# slaveV10a.net
KiCad netlist of a schematic drawn in EAGLE
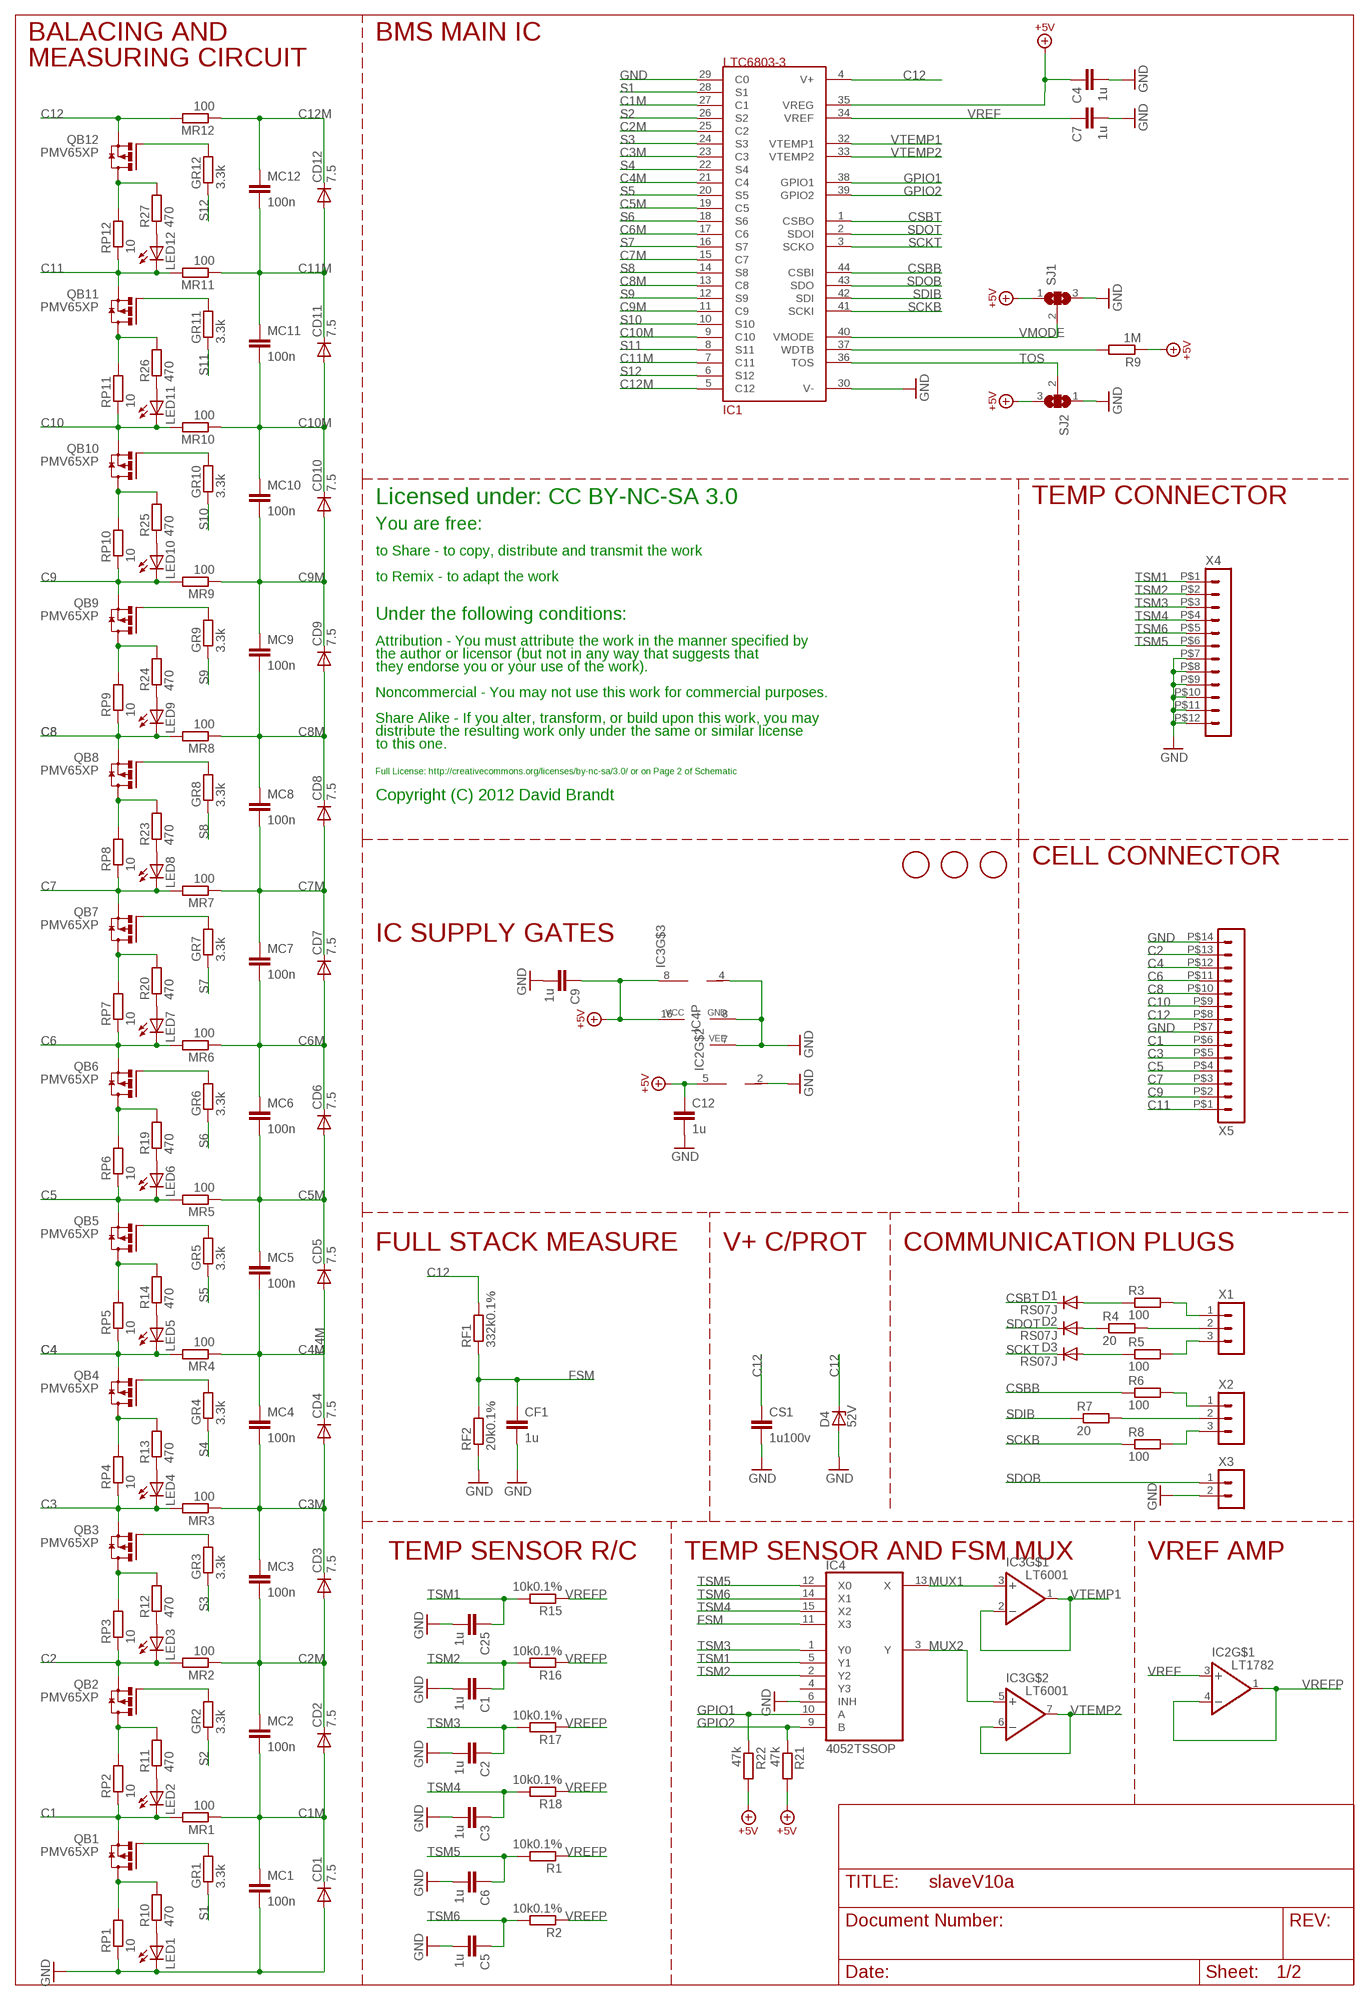
[diagram p0: schematic, sheet 1]
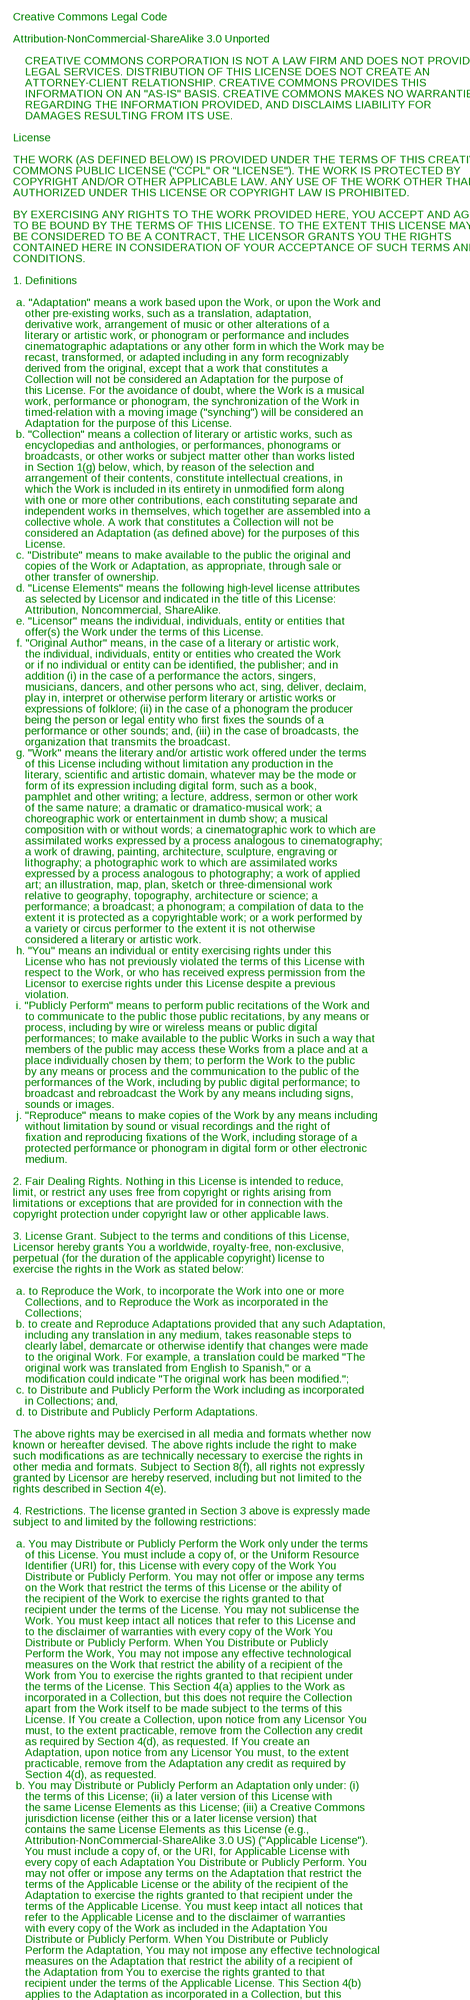
[diagram p1: schematic, sheet 2, part 1 of 2]
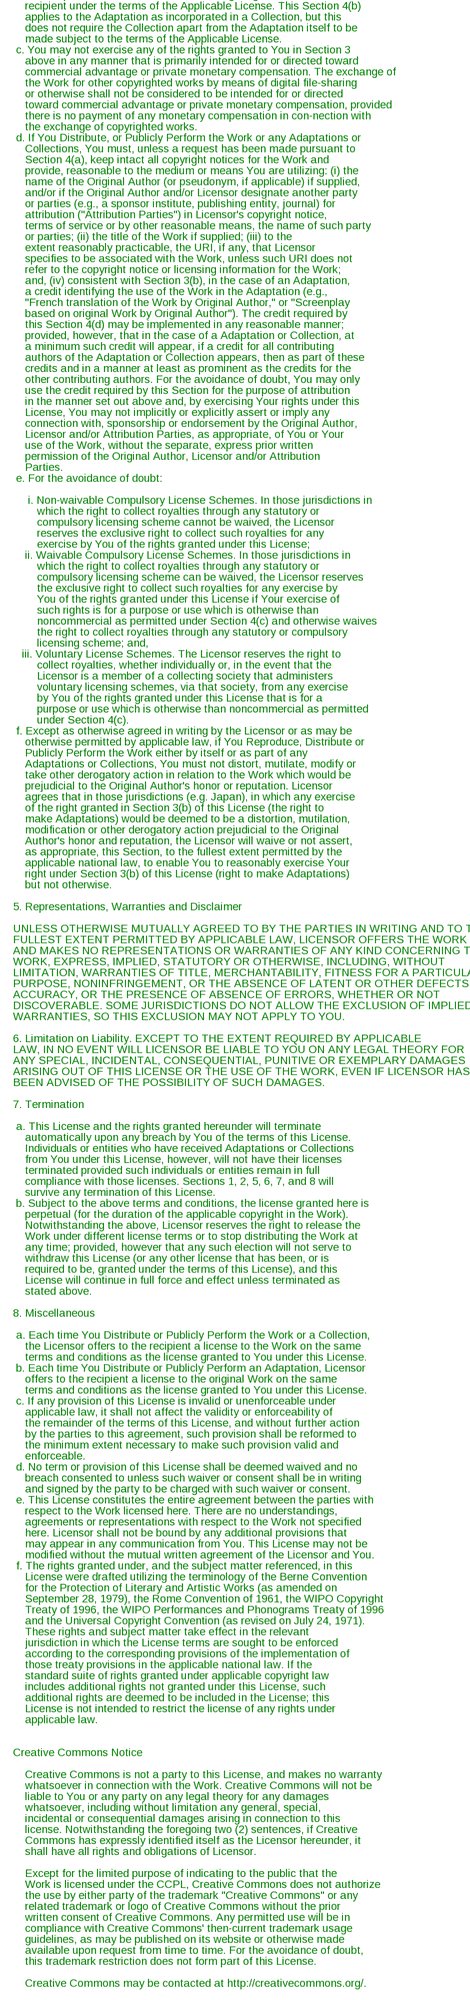
[diagram p2: schematic, sheet 2, part 2 of 2]

(export (version "E")
  (design (tool "Eeschema 10.0.6"))
  (components
    (comp (ref "C1")
      (value "1u")
      (footprint "eagle-import:C0603")
      (libsource (lib "eagle-import") (part "C-EUC0603"))
    )
    (comp (ref "C2")
      (value "1u")
      (footprint "eagle-import:C0603")
      (libsource (lib "eagle-import") (part "C-EUC0603"))
    )
    (comp (ref "C3")
      (value "1u")
      (footprint "eagle-import:C0603")
      (libsource (lib "eagle-import") (part "C-EUC0603"))
    )
    (comp (ref "C4")
      (value "1u")
      (footprint "eagle-import:C0603")
      (libsource (lib "eagle-import") (part "C-EUC0603"))
    )
    (comp (ref "C5")
      (value "1u")
      (footprint "eagle-import:C0603")
      (libsource (lib "eagle-import") (part "C-EUC0603"))
    )
    (comp (ref "C6")
      (value "1u")
      (footprint "eagle-import:C0603")
      (libsource (lib "eagle-import") (part "C-EUC0603"))
    )
    (comp (ref "C7")
      (value "1u")
      (footprint "eagle-import:C0603")
      (libsource (lib "eagle-import") (part "C-EUC0603"))
    )
    (comp (ref "C9")
      (value "1u")
      (footprint "eagle-import:C0603")
      (libsource (lib "eagle-import") (part "C-EUC0603"))
    )
    (comp (ref "C12")
      (value "1u")
      (footprint "eagle-import:C0603")
      (libsource (lib "eagle-import") (part "C-EUC0603"))
    )
    (comp (ref "C25")
      (value "1u")
      (footprint "eagle-import:C0603")
      (libsource (lib "eagle-import") (part "C-EUC0603"))
    )
    (comp (ref "CD1")
      (value "7.5")
      (footprint "eagle-import:SOD323-W")
      (libsource (lib "eagle-import") (part "DIODE-SOD323-W"))
    )
    (comp (ref "CD2")
      (value "7.5")
      (footprint "eagle-import:SOD323-W")
      (libsource (lib "eagle-import") (part "DIODE-SOD323-W"))
    )
    (comp (ref "CD3")
      (value "7.5")
      (footprint "eagle-import:SOD323-W")
      (libsource (lib "eagle-import") (part "DIODE-SOD323-W"))
    )
    (comp (ref "CD4")
      (value "7.5")
      (footprint "eagle-import:SOD323-W")
      (libsource (lib "eagle-import") (part "DIODE-SOD323-W"))
    )
    (comp (ref "CD5")
      (value "7.5")
      (footprint "eagle-import:SOD323-W")
      (libsource (lib "eagle-import") (part "DIODE-SOD323-W"))
    )
    (comp (ref "CD6")
      (value "7.5")
      (footprint "eagle-import:SOD323-W")
      (libsource (lib "eagle-import") (part "DIODE-SOD323-W"))
    )
    (comp (ref "CD7")
      (value "7.5")
      (footprint "eagle-import:SOD323-W")
      (libsource (lib "eagle-import") (part "DIODE-SOD323-W"))
    )
    (comp (ref "CD8")
      (value "7.5")
      (footprint "eagle-import:SOD323-W")
      (libsource (lib "eagle-import") (part "DIODE-SOD323-W"))
    )
    (comp (ref "CD9")
      (value "7.5")
      (footprint "eagle-import:SOD323-W")
      (libsource (lib "eagle-import") (part "DIODE-SOD323-W"))
    )
    (comp (ref "CD10")
      (value "7.5")
      (footprint "eagle-import:SOD323-W")
      (libsource (lib "eagle-import") (part "DIODE-SOD323-W"))
    )
    (comp (ref "CD11")
      (value "7.5")
      (footprint "eagle-import:SOD323-W")
      (libsource (lib "eagle-import") (part "DIODE-SOD323-W"))
    )
    (comp (ref "CD12")
      (value "7.5")
      (footprint "eagle-import:SOD323-W")
      (libsource (lib "eagle-import") (part "DIODE-SOD323-W"))
    )
    (comp (ref "CF1")
      (value "1u")
      (footprint "eagle-import:C0603")
      (libsource (lib "eagle-import") (part "C-EUC0603"))
    )
    (comp (ref "CS1")
      (value "1u100v")
      (footprint "eagle-import:C1206K")
      (libsource (lib "eagle-import") (part "C-EUC1206K"))
    )
    (comp (ref "D1")
      (value "RS07J")
      (footprint "eagle-import:DO-219AB")
      (libsource (lib "eagle-import") (part "RS07J"))
    )
    (comp (ref "D2")
      (value "RS07J")
      (footprint "eagle-import:DO-219AB")
      (libsource (lib "eagle-import") (part "RS07J"))
    )
    (comp (ref "D3")
      (value "RS07J")
      (footprint "eagle-import:DO-219AB")
      (libsource (lib "eagle-import") (part "RS07J"))
    )
    (comp (ref "D4")
      (value "52V")
      (footprint "eagle-import:SOD123")
      (libsource (lib "eagle-import") (part "ZENER-DIODESOD123"))
    )
    (comp (ref "GR1")
      (value "3.3k")
      (footprint "eagle-import:R0603")
      (libsource (lib "eagle-import") (part "rcl_R-EU_R0603"))
    )
    (comp (ref "GR2")
      (value "3.3k")
      (footprint "eagle-import:R0603")
      (libsource (lib "eagle-import") (part "rcl_R-EU_R0603"))
    )
    (comp (ref "GR3")
      (value "3.3k")
      (footprint "eagle-import:R0603")
      (libsource (lib "eagle-import") (part "rcl_R-EU_R0603"))
    )
    (comp (ref "GR4")
      (value "3.3k")
      (footprint "eagle-import:R0603")
      (libsource (lib "eagle-import") (part "rcl_R-EU_R0603"))
    )
    (comp (ref "GR5")
      (value "3.3k")
      (footprint "eagle-import:R0603")
      (libsource (lib "eagle-import") (part "rcl_R-EU_R0603"))
    )
    (comp (ref "GR6")
      (value "3.3k")
      (footprint "eagle-import:R0603")
      (libsource (lib "eagle-import") (part "rcl_R-EU_R0603"))
    )
    (comp (ref "GR7")
      (value "3.3k")
      (footprint "eagle-import:R0603")
      (libsource (lib "eagle-import") (part "rcl_R-EU_R0603"))
    )
    (comp (ref "GR8")
      (value "3.3k")
      (footprint "eagle-import:R0603")
      (libsource (lib "eagle-import") (part "rcl_R-EU_R0603"))
    )
    (comp (ref "GR9")
      (value "3.3k")
      (footprint "eagle-import:R0603")
      (libsource (lib "eagle-import") (part "rcl_R-EU_R0603"))
    )
    (comp (ref "GR10")
      (value "3.3k")
      (footprint "eagle-import:R0603")
      (libsource (lib "eagle-import") (part "rcl_R-EU_R0603"))
    )
    (comp (ref "GR11")
      (value "3.3k")
      (footprint "eagle-import:R0603")
      (libsource (lib "eagle-import") (part "rcl_R-EU_R0603"))
    )
    (comp (ref "GR12")
      (value "3.3k")
      (footprint "eagle-import:R0603")
      (libsource (lib "eagle-import") (part "rcl_R-EU_R0603"))
    )
    (comp (ref "IC1")
      (value "LTC6803-3")
      (footprint "eagle-import:44SSOP")
      (libsource (lib "eagle-import") (part "LTC6803-3"))
    )
    (comp (ref "IC2")
      (value "LT1782")
      (footprint "eagle-import:SOT23-5")
      (libsource (lib "eagle-import") (part "LT1782"))
    )
    (comp (ref "IC3")
      (value "LT6001")
      (footprint "eagle-import:MS8")
      (libsource (lib "eagle-import") (part "LT6004"))
    )
    (comp (ref "IC4")
      (value "4052TSSOP")
      (footprint "eagle-import:TSSOP16")
      (libsource (lib "eagle-import") (part "4052TSSOP"))
    )
    (comp (ref "LED1")
      (value "LEDCHIPLED_0805")
      (footprint "eagle-import:CHIPLED_0805")
      (libsource (lib "eagle-import") (part "LEDCHIPLED_0805"))
    )
    (comp (ref "LED2")
      (value "LEDCHIPLED_0805")
      (footprint "eagle-import:CHIPLED_0805")
      (libsource (lib "eagle-import") (part "LEDCHIPLED_0805"))
    )
    (comp (ref "LED3")
      (value "LEDCHIPLED_0805")
      (footprint "eagle-import:CHIPLED_0805")
      (libsource (lib "eagle-import") (part "LEDCHIPLED_0805"))
    )
    (comp (ref "LED4")
      (value "LEDCHIPLED_0805")
      (footprint "eagle-import:CHIPLED_0805")
      (libsource (lib "eagle-import") (part "LEDCHIPLED_0805"))
    )
    (comp (ref "LED5")
      (value "LEDCHIPLED_0805")
      (footprint "eagle-import:CHIPLED_0805")
      (libsource (lib "eagle-import") (part "LEDCHIPLED_0805"))
    )
    (comp (ref "LED6")
      (value "LEDCHIPLED_0805")
      (footprint "eagle-import:CHIPLED_0805")
      (libsource (lib "eagle-import") (part "LEDCHIPLED_0805"))
    )
    (comp (ref "LED7")
      (value "LEDCHIPLED_0805")
      (footprint "eagle-import:CHIPLED_0805")
      (libsource (lib "eagle-import") (part "LEDCHIPLED_0805"))
    )
    (comp (ref "LED8")
      (value "LEDCHIPLED_0805")
      (footprint "eagle-import:CHIPLED_0805")
      (libsource (lib "eagle-import") (part "LEDCHIPLED_0805"))
    )
    (comp (ref "LED9")
      (value "LEDCHIPLED_0805")
      (footprint "eagle-import:CHIPLED_0805")
      (libsource (lib "eagle-import") (part "LEDCHIPLED_0805"))
    )
    (comp (ref "LED10")
      (value "LEDCHIPLED_0805")
      (footprint "eagle-import:CHIPLED_0805")
      (libsource (lib "eagle-import") (part "LEDCHIPLED_0805"))
    )
    (comp (ref "LED11")
      (value "LEDCHIPLED_0805")
      (footprint "eagle-import:CHIPLED_0805")
      (libsource (lib "eagle-import") (part "LEDCHIPLED_0805"))
    )
    (comp (ref "LED12")
      (value "LEDCHIPLED_0805")
      (footprint "eagle-import:CHIPLED_0805")
      (libsource (lib "eagle-import") (part "LEDCHIPLED_0805"))
    )
    (comp (ref "MC1")
      (value "100n")
      (footprint "eagle-import:C1206")
      (libsource (lib "eagle-import") (part "C-EUC1206"))
    )
    (comp (ref "MC2")
      (value "100n")
      (footprint "eagle-import:C1206")
      (libsource (lib "eagle-import") (part "C-EUC1206"))
    )
    (comp (ref "MC3")
      (value "100n")
      (footprint "eagle-import:C1206")
      (libsource (lib "eagle-import") (part "C-EUC1206"))
    )
    (comp (ref "MC4")
      (value "100n")
      (footprint "eagle-import:C1206")
      (libsource (lib "eagle-import") (part "C-EUC1206"))
    )
    (comp (ref "MC5")
      (value "100n")
      (footprint "eagle-import:C1206")
      (libsource (lib "eagle-import") (part "C-EUC1206"))
    )
    (comp (ref "MC6")
      (value "100n")
      (footprint "eagle-import:C1206")
      (libsource (lib "eagle-import") (part "C-EUC1206"))
    )
    (comp (ref "MC7")
      (value "100n")
      (footprint "eagle-import:C1206")
      (libsource (lib "eagle-import") (part "C-EUC1206"))
    )
    (comp (ref "MC8")
      (value "100n")
      (footprint "eagle-import:C1206")
      (libsource (lib "eagle-import") (part "C-EUC1206"))
    )
    (comp (ref "MC9")
      (value "100n")
      (footprint "eagle-import:C1206")
      (libsource (lib "eagle-import") (part "C-EUC1206"))
    )
    (comp (ref "MC10")
      (value "100n")
      (footprint "eagle-import:C1206")
      (libsource (lib "eagle-import") (part "C-EUC1206"))
    )
    (comp (ref "MC11")
      (value "100n")
      (footprint "eagle-import:C1206")
      (libsource (lib "eagle-import") (part "C-EUC1206"))
    )
    (comp (ref "MC12")
      (value "100n")
      (footprint "eagle-import:C1206")
      (libsource (lib "eagle-import") (part "C-EUC1206"))
    )
    (comp (ref "MR1")
      (value "100")
      (footprint "eagle-import:R0603")
      (libsource (lib "eagle-import") (part "rcl_R-EU_R0603"))
    )
    (comp (ref "MR2")
      (value "100")
      (footprint "eagle-import:R0603")
      (libsource (lib "eagle-import") (part "rcl_R-EU_R0603"))
    )
    (comp (ref "MR3")
      (value "100")
      (footprint "eagle-import:R0603")
      (libsource (lib "eagle-import") (part "rcl_R-EU_R0603"))
    )
    (comp (ref "MR4")
      (value "100")
      (footprint "eagle-import:R0603")
      (libsource (lib "eagle-import") (part "rcl_R-EU_R0603"))
    )
    (comp (ref "MR5")
      (value "100")
      (footprint "eagle-import:R0603")
      (libsource (lib "eagle-import") (part "rcl_R-EU_R0603"))
    )
    (comp (ref "MR6")
      (value "100")
      (footprint "eagle-import:R0603")
      (libsource (lib "eagle-import") (part "rcl_R-EU_R0603"))
    )
    (comp (ref "MR7")
      (value "100")
      (footprint "eagle-import:R0603")
      (libsource (lib "eagle-import") (part "rcl_R-EU_R0603"))
    )
    (comp (ref "MR8")
      (value "100")
      (footprint "eagle-import:R0603")
      (libsource (lib "eagle-import") (part "rcl_R-EU_R0603"))
    )
    (comp (ref "MR9")
      (value "100")
      (footprint "eagle-import:R0603")
      (libsource (lib "eagle-import") (part "rcl_R-EU_R0603"))
    )
    (comp (ref "MR10")
      (value "100")
      (footprint "eagle-import:R0603")
      (libsource (lib "eagle-import") (part "rcl_R-EU_R0603"))
    )
    (comp (ref "MR11")
      (value "100")
      (footprint "eagle-import:R0603")
      (libsource (lib "eagle-import") (part "rcl_R-EU_R0603"))
    )
    (comp (ref "MR12")
      (value "100")
      (footprint "eagle-import:R0603")
      (libsource (lib "eagle-import") (part "rcl_R-EU_R0603"))
    )
    (comp (ref "QB1")
      (value "PMV65XP")
      (footprint "eagle-import:SUPER-SOT3")
      (libsource (lib "eagle-import") (part "FDN360P"))
    )
    (comp (ref "QB2")
      (value "PMV65XP")
      (footprint "eagle-import:SUPER-SOT3")
      (libsource (lib "eagle-import") (part "FDN360P"))
    )
    (comp (ref "QB3")
      (value "PMV65XP")
      (footprint "eagle-import:SUPER-SOT3")
      (libsource (lib "eagle-import") (part "FDN360P"))
    )
    (comp (ref "QB4")
      (value "PMV65XP")
      (footprint "eagle-import:SUPER-SOT3")
      (libsource (lib "eagle-import") (part "FDN360P"))
    )
    (comp (ref "QB5")
      (value "PMV65XP")
      (footprint "eagle-import:SUPER-SOT3")
      (libsource (lib "eagle-import") (part "FDN360P"))
    )
    (comp (ref "QB6")
      (value "PMV65XP")
      (footprint "eagle-import:SUPER-SOT3")
      (libsource (lib "eagle-import") (part "FDN360P"))
    )
    (comp (ref "QB7")
      (value "PMV65XP")
      (footprint "eagle-import:SUPER-SOT3")
      (libsource (lib "eagle-import") (part "FDN360P"))
    )
    (comp (ref "QB8")
      (value "PMV65XP")
      (footprint "eagle-import:SUPER-SOT3")
      (libsource (lib "eagle-import") (part "FDN360P"))
    )
    (comp (ref "QB9")
      (value "PMV65XP")
      (footprint "eagle-import:SUPER-SOT3")
      (libsource (lib "eagle-import") (part "FDN360P"))
    )
    (comp (ref "QB10")
      (value "PMV65XP")
      (footprint "eagle-import:SUPER-SOT3")
      (libsource (lib "eagle-import") (part "FDN360P"))
    )
    (comp (ref "QB11")
      (value "PMV65XP")
      (footprint "eagle-import:SUPER-SOT3")
      (libsource (lib "eagle-import") (part "FDN360P"))
    )
    (comp (ref "QB12")
      (value "PMV65XP")
      (footprint "eagle-import:SUPER-SOT3")
      (libsource (lib "eagle-import") (part "FDN360P"))
    )
    (comp (ref "R1")
      (value "10k0.1%")
      (footprint "eagle-import:R0603")
      (libsource (lib "eagle-import") (part "rcl_R-EU_R0603"))
    )
    (comp (ref "R2")
      (value "10k0.1%")
      (footprint "eagle-import:R0603")
      (libsource (lib "eagle-import") (part "rcl_R-EU_R0603"))
    )
    (comp (ref "R3")
      (value "100")
      (footprint "eagle-import:R0805")
      (libsource (lib "eagle-import") (part "rcl_R-EU_R0805"))
    )
    (comp (ref "R4")
      (value "20")
      (footprint "eagle-import:R0805")
      (libsource (lib "eagle-import") (part "rcl_R-EU_R0805"))
    )
    (comp (ref "R5")
      (value "100")
      (footprint "eagle-import:R0805")
      (libsource (lib "eagle-import") (part "rcl_R-EU_R0805"))
    )
    (comp (ref "R6")
      (value "100")
      (footprint "eagle-import:R0805")
      (libsource (lib "eagle-import") (part "rcl_R-EU_R0805"))
    )
    (comp (ref "R7")
      (value "20")
      (footprint "eagle-import:R0805")
      (libsource (lib "eagle-import") (part "rcl_R-EU_R0805"))
    )
    (comp (ref "R8")
      (value "100")
      (footprint "eagle-import:R0805")
      (libsource (lib "eagle-import") (part "rcl_R-EU_R0805"))
    )
    (comp (ref "R9")
      (value "1M")
      (footprint "eagle-import:R0603")
      (libsource (lib "eagle-import") (part "rcl_R-EU_R0603"))
    )
    (comp (ref "R10")
      (value "470")
      (footprint "eagle-import:R0603")
      (libsource (lib "eagle-import") (part "rcl_R-EU_R0603"))
    )
    (comp (ref "R11")
      (value "470")
      (footprint "eagle-import:R0603")
      (libsource (lib "eagle-import") (part "rcl_R-EU_R0603"))
    )
    (comp (ref "R12")
      (value "470")
      (footprint "eagle-import:R0603")
      (libsource (lib "eagle-import") (part "rcl_R-EU_R0603"))
    )
    (comp (ref "R13")
      (value "470")
      (footprint "eagle-import:R0603")
      (libsource (lib "eagle-import") (part "rcl_R-EU_R0603"))
    )
    (comp (ref "R14")
      (value "470")
      (footprint "eagle-import:R0603")
      (libsource (lib "eagle-import") (part "rcl_R-EU_R0603"))
    )
    (comp (ref "R15")
      (value "10k0.1%")
      (footprint "eagle-import:R0603")
      (libsource (lib "eagle-import") (part "rcl_R-EU_R0603"))
    )
    (comp (ref "R16")
      (value "10k0.1%")
      (footprint "eagle-import:R0603")
      (libsource (lib "eagle-import") (part "rcl_R-EU_R0603"))
    )
    (comp (ref "R17")
      (value "10k0.1%")
      (footprint "eagle-import:R0603")
      (libsource (lib "eagle-import") (part "rcl_R-EU_R0603"))
    )
    (comp (ref "R18")
      (value "10k0.1%")
      (footprint "eagle-import:R0603")
      (libsource (lib "eagle-import") (part "rcl_R-EU_R0603"))
    )
    (comp (ref "R19")
      (value "470")
      (footprint "eagle-import:R0603")
      (libsource (lib "eagle-import") (part "rcl_R-EU_R0603"))
    )
    (comp (ref "R20")
      (value "470")
      (footprint "eagle-import:R0603")
      (libsource (lib "eagle-import") (part "rcl_R-EU_R0603"))
    )
    (comp (ref "R21")
      (value "47k")
      (footprint "eagle-import:R0603")
      (libsource (lib "eagle-import") (part "rcl_R-EU_R0603"))
    )
    (comp (ref "R22")
      (value "47k")
      (footprint "eagle-import:R0603")
      (libsource (lib "eagle-import") (part "rcl_R-EU_R0603"))
    )
    (comp (ref "R23")
      (value "470")
      (footprint "eagle-import:R0603")
      (libsource (lib "eagle-import") (part "rcl_R-EU_R0603"))
    )
    (comp (ref "R24")
      (value "470")
      (footprint "eagle-import:R0603")
      (libsource (lib "eagle-import") (part "rcl_R-EU_R0603"))
    )
    (comp (ref "R25")
      (value "470")
      (footprint "eagle-import:R0603")
      (libsource (lib "eagle-import") (part "rcl_R-EU_R0603"))
    )
    (comp (ref "R26")
      (value "470")
      (footprint "eagle-import:R0603")
      (libsource (lib "eagle-import") (part "rcl_R-EU_R0603"))
    )
    (comp (ref "R27")
      (value "470")
      (footprint "eagle-import:R0603")
      (libsource (lib "eagle-import") (part "rcl_R-EU_R0603"))
    )
    (comp (ref "REF1")
      (value "FIDUCIALMOUNT")
      (footprint "eagle-import:FIDUCIA-MOUNT")
      (libsource (lib "eagle-import") (part "FIDUCIALMOUNT"))
    )
    (comp (ref "REF2")
      (value "FIDUCIALMOUNT")
      (footprint "eagle-import:FIDUCIA-MOUNT")
      (libsource (lib "eagle-import") (part "FIDUCIALMOUNT"))
    )
    (comp (ref "REF3")
      (value "FIDUCIALMOUNT")
      (footprint "eagle-import:FIDUCIA-MOUNT")
      (libsource (lib "eagle-import") (part "FIDUCIALMOUNT"))
    )
    (comp (ref "RF1")
      (value "332k0.1%")
      (footprint "eagle-import:R0603")
      (libsource (lib "eagle-import") (part "rcl_R-EU_R0603"))
    )
    (comp (ref "RF2")
      (value "20k0.1%")
      (footprint "eagle-import:R0603")
      (libsource (lib "eagle-import") (part "rcl_R-EU_R0603"))
    )
    (comp (ref "RP1")
      (value "10")
      (footprint "eagle-import:SM_3")
      (libsource (lib "eagle-import") (part "R-EU_SM_3"))
    )
    (comp (ref "RP2")
      (value "10")
      (footprint "eagle-import:SM_3")
      (libsource (lib "eagle-import") (part "R-EU_SM_3"))
    )
    (comp (ref "RP3")
      (value "10")
      (footprint "eagle-import:SM_3")
      (libsource (lib "eagle-import") (part "R-EU_SM_3"))
    )
    (comp (ref "RP4")
      (value "10")
      (footprint "eagle-import:SM_3")
      (libsource (lib "eagle-import") (part "R-EU_SM_3"))
    )
    (comp (ref "RP5")
      (value "10")
      (footprint "eagle-import:SM_3")
      (libsource (lib "eagle-import") (part "R-EU_SM_3"))
    )
    (comp (ref "RP6")
      (value "10")
      (footprint "eagle-import:SM_3")
      (libsource (lib "eagle-import") (part "R-EU_SM_3"))
    )
    (comp (ref "RP7")
      (value "10")
      (footprint "eagle-import:SM_3")
      (libsource (lib "eagle-import") (part "R-EU_SM_3"))
    )
    (comp (ref "RP8")
      (value "10")
      (footprint "eagle-import:SM_3")
      (libsource (lib "eagle-import") (part "R-EU_SM_3"))
    )
    (comp (ref "RP9")
      (value "10")
      (footprint "eagle-import:SM_3")
      (libsource (lib "eagle-import") (part "R-EU_SM_3"))
    )
    (comp (ref "RP10")
      (value "10")
      (footprint "eagle-import:SM_3")
      (libsource (lib "eagle-import") (part "R-EU_SM_3"))
    )
    (comp (ref "RP11")
      (value "10")
      (footprint "eagle-import:SM_3")
      (libsource (lib "eagle-import") (part "R-EU_SM_3"))
    )
    (comp (ref "RP12")
      (value "10")
      (footprint "eagle-import:SM_3")
      (libsource (lib "eagle-import") (part "R-EU_SM_3"))
    )
    (comp (ref "SJ1")
      (value "SJ2W")
      (footprint "eagle-import:SJ_2")
      (libsource (lib "eagle-import") (part "SJ2W"))
    )
    (comp (ref "SJ2")
      (value "SJ2W")
      (footprint "eagle-import:SJ_2")
      (libsource (lib "eagle-import") (part "SJ2W"))
    )
    (comp (ref "X1")
      (value "HEADER_POS3_43650-0315")
      (footprint "eagle-import:43650-0315")
      (libsource (lib "eagle-import") (part "HEADER_POS3_?43650-0315"))
    )
    (comp (ref "X2")
      (value "HEADER_POS3_43650-0315")
      (footprint "eagle-import:43650-0315")
      (libsource (lib "eagle-import") (part "HEADER_POS3_?43650-0315"))
    )
    (comp (ref "X3")
      (value "HEADER_POS2_43650-0215")
      (footprint "eagle-import:43650-0215")
      (libsource (lib "eagle-import") (part "HEADER_POS2_?43650-0215"))
    )
    (comp (ref "X4")
      (value "HEADER_POS12_43045-1212")
      (footprint "eagle-import:43045-1212")
      (libsource (lib "eagle-import") (part "HEADER_POS12_?43045-1212"))
    )
    (comp (ref "X5")
      (value "HEADER_POS14_43045-1412")
      (footprint "eagle-import:43045-1412")
      (libsource (lib "eagle-import") (part "HEADER_POS14_?43045-1412"))
    )
  )
  (nets
    (net (code "1") (name "+5V") (class "Default")
      (node (ref "C12") (pin "1") (pinfunction "1_1") (pintype "passive"))
      (node (ref "C4") (pin "1") (pinfunction "1_1") (pintype "passive"))
      (node (ref "C9") (pin "1") (pinfunction "1_1") (pintype "passive"))
      (node (ref "IC1") (pin "35") (pinfunction "VREG_35") (pintype "bidirectional"))
      (node (ref "IC2") (pin "5") (pinfunction "V+_5") (pintype "power_in"))
      (node (ref "IC3") (pin "8") (pinfunction "V+_8") (pintype "power_in"))
      (node (ref "IC4") (pin "16") (pinfunction "VCC_16") (pintype "power_in"))
      (node (ref "R21") (pin "2") (pinfunction "2_2") (pintype "passive"))
      (node (ref "R22") (pin "2") (pinfunction "2_2") (pintype "passive"))
      (node (ref "R9") (pin "1") (pinfunction "1_1") (pintype "passive"))
      (node (ref "SJ1") (pin "1") (pinfunction "1_1") (pintype "passive"))
      (node (ref "SJ2") (pin "3") (pinfunction "3_3") (pintype "passive"))
    )
    (net (code "2") (name "C1") (class "Default")
      (node (ref "LED2") (pin "C") (pinfunction "C_C") (pintype "passive"))
      (node (ref "MR1") (pin "2") (pinfunction "2_2") (pintype "passive"))
      (node (ref "QB1") (pin "2") (pinfunction "S_2") (pintype "passive"))
      (node (ref "RP2") (pin "P$1") (pinfunction "1_P$1") (pintype "passive"))
      (node (ref "X5") (pin "P$6") (pinfunction "6_P$6") (pintype "passive"))
    )
    (net (code "3") (name "C1M") (class "Default")
      (node (ref "CD1") (pin "C") (pinfunction "C_C") (pintype "passive"))
      (node (ref "CD2") (pin "A") (pinfunction "A_A") (pintype "passive"))
      (node (ref "IC1") (pin "27") (pinfunction "C1_27") (pintype "bidirectional"))
      (node (ref "MC1") (pin "1") (pinfunction "1_1") (pintype "passive"))
      (node (ref "MC2") (pin "2") (pinfunction "2_2") (pintype "passive"))
      (node (ref "MR1") (pin "1") (pinfunction "1_1") (pintype "passive"))
    )
    (net (code "4") (name "C2") (class "Default")
      (node (ref "LED3") (pin "C") (pinfunction "C_C") (pintype "passive"))
      (node (ref "MR2") (pin "2") (pinfunction "2_2") (pintype "passive"))
      (node (ref "QB2") (pin "2") (pinfunction "S_2") (pintype "passive"))
      (node (ref "RP3") (pin "P$1") (pinfunction "1_P$1") (pintype "passive"))
      (node (ref "X5") (pin "P$13") (pinfunction "13_P$13") (pintype "passive"))
    )
    (net (code "5") (name "C2M") (class "Default")
      (node (ref "CD2") (pin "C") (pinfunction "C_C") (pintype "passive"))
      (node (ref "CD3") (pin "A") (pinfunction "A_A") (pintype "passive"))
      (node (ref "IC1") (pin "25") (pinfunction "C2_25") (pintype "bidirectional"))
      (node (ref "MC2") (pin "1") (pinfunction "1_1") (pintype "passive"))
      (node (ref "MC3") (pin "2") (pinfunction "2_2") (pintype "passive"))
      (node (ref "MR2") (pin "1") (pinfunction "1_1") (pintype "passive"))
    )
    (net (code "6") (name "C3") (class "Default")
      (node (ref "LED4") (pin "C") (pinfunction "C_C") (pintype "passive"))
      (node (ref "MR3") (pin "2") (pinfunction "2_2") (pintype "passive"))
      (node (ref "QB3") (pin "2") (pinfunction "S_2") (pintype "passive"))
      (node (ref "RP4") (pin "P$1") (pinfunction "1_P$1") (pintype "passive"))
      (node (ref "X5") (pin "P$5") (pinfunction "5_P$5") (pintype "passive"))
    )
    (net (code "7") (name "C3M") (class "Default")
      (node (ref "CD3") (pin "C") (pinfunction "C_C") (pintype "passive"))
      (node (ref "CD4") (pin "A") (pinfunction "A_A") (pintype "passive"))
      (node (ref "IC1") (pin "23") (pinfunction "C3_23") (pintype "bidirectional"))
      (node (ref "MC3") (pin "1") (pinfunction "1_1") (pintype "passive"))
      (node (ref "MC4") (pin "2") (pinfunction "2_2") (pintype "passive"))
      (node (ref "MR3") (pin "1") (pinfunction "1_1") (pintype "passive"))
    )
    (net (code "8") (name "C4") (class "Default")
      (node (ref "LED5") (pin "C") (pinfunction "C_C") (pintype "passive"))
      (node (ref "MR4") (pin "2") (pinfunction "2_2") (pintype "passive"))
      (node (ref "QB4") (pin "2") (pinfunction "S_2") (pintype "passive"))
      (node (ref "RP5") (pin "P$1") (pinfunction "1_P$1") (pintype "passive"))
      (node (ref "X5") (pin "P$12") (pinfunction "12_P$12") (pintype "passive"))
    )
    (net (code "9") (name "C4M") (class "Default")
      (node (ref "CD4") (pin "C") (pinfunction "C_C") (pintype "passive"))
      (node (ref "CD5") (pin "A") (pinfunction "A_A") (pintype "passive"))
      (node (ref "IC1") (pin "21") (pinfunction "C4_21") (pintype "bidirectional"))
      (node (ref "MC4") (pin "1") (pinfunction "1_1") (pintype "passive"))
      (node (ref "MC5") (pin "2") (pinfunction "2_2") (pintype "passive"))
      (node (ref "MR4") (pin "1") (pinfunction "1_1") (pintype "passive"))
    )
    (net (code "10") (name "C5") (class "Default")
      (node (ref "LED6") (pin "C") (pinfunction "C_C") (pintype "passive"))
      (node (ref "MR5") (pin "2") (pinfunction "2_2") (pintype "passive"))
      (node (ref "QB5") (pin "2") (pinfunction "S_2") (pintype "passive"))
      (node (ref "RP6") (pin "P$1") (pinfunction "1_P$1") (pintype "passive"))
      (node (ref "X5") (pin "P$4") (pinfunction "4_P$4") (pintype "passive"))
    )
    (net (code "11") (name "C5M") (class "Default")
      (node (ref "CD5") (pin "C") (pinfunction "C_C") (pintype "passive"))
      (node (ref "CD6") (pin "A") (pinfunction "A_A") (pintype "passive"))
      (node (ref "IC1") (pin "19") (pinfunction "C5_19") (pintype "bidirectional"))
      (node (ref "MC5") (pin "1") (pinfunction "1_1") (pintype "passive"))
      (node (ref "MC6") (pin "2") (pinfunction "2_2") (pintype "passive"))
      (node (ref "MR5") (pin "1") (pinfunction "1_1") (pintype "passive"))
    )
    (net (code "12") (name "C6") (class "Default")
      (node (ref "LED7") (pin "C") (pinfunction "C_C") (pintype "passive"))
      (node (ref "MR6") (pin "2") (pinfunction "2_2") (pintype "passive"))
      (node (ref "QB6") (pin "2") (pinfunction "S_2") (pintype "passive"))
      (node (ref "RP7") (pin "P$1") (pinfunction "1_P$1") (pintype "passive"))
      (node (ref "X5") (pin "P$11") (pinfunction "11_P$11") (pintype "passive"))
    )
    (net (code "13") (name "C6M") (class "Default")
      (node (ref "CD6") (pin "C") (pinfunction "C_C") (pintype "passive"))
      (node (ref "CD7") (pin "A") (pinfunction "A_A") (pintype "passive"))
      (node (ref "IC1") (pin "17") (pinfunction "C6_17") (pintype "bidirectional"))
      (node (ref "MC6") (pin "1") (pinfunction "1_1") (pintype "passive"))
      (node (ref "MC7") (pin "2") (pinfunction "2_2") (pintype "passive"))
      (node (ref "MR6") (pin "1") (pinfunction "1_1") (pintype "passive"))
    )
    (net (code "14") (name "C7") (class "Default")
      (node (ref "LED8") (pin "C") (pinfunction "C_C") (pintype "passive"))
      (node (ref "MR7") (pin "2") (pinfunction "2_2") (pintype "passive"))
      (node (ref "QB7") (pin "2") (pinfunction "S_2") (pintype "passive"))
      (node (ref "RP8") (pin "P$1") (pinfunction "1_P$1") (pintype "passive"))
      (node (ref "X5") (pin "P$3") (pinfunction "3_P$3") (pintype "passive"))
    )
    (net (code "15") (name "C7M") (class "Default")
      (node (ref "CD7") (pin "C") (pinfunction "C_C") (pintype "passive"))
      (node (ref "CD8") (pin "A") (pinfunction "A_A") (pintype "passive"))
      (node (ref "IC1") (pin "15") (pinfunction "C7_15") (pintype "bidirectional"))
      (node (ref "MC7") (pin "1") (pinfunction "1_1") (pintype "passive"))
      (node (ref "MC8") (pin "2") (pinfunction "2_2") (pintype "passive"))
      (node (ref "MR7") (pin "1") (pinfunction "1_1") (pintype "passive"))
    )
    (net (code "16") (name "C8") (class "Default")
      (node (ref "LED9") (pin "C") (pinfunction "C_C") (pintype "passive"))
      (node (ref "MR8") (pin "2") (pinfunction "2_2") (pintype "passive"))
      (node (ref "QB8") (pin "2") (pinfunction "S_2") (pintype "passive"))
      (node (ref "RP9") (pin "P$1") (pinfunction "1_P$1") (pintype "passive"))
      (node (ref "X5") (pin "P$10") (pinfunction "10_P$10") (pintype "passive"))
    )
    (net (code "17") (name "C8M") (class "Default")
      (node (ref "CD8") (pin "C") (pinfunction "C_C") (pintype "passive"))
      (node (ref "CD9") (pin "A") (pinfunction "A_A") (pintype "passive"))
      (node (ref "IC1") (pin "13") (pinfunction "C8_13") (pintype "bidirectional"))
      (node (ref "MC8") (pin "1") (pinfunction "1_1") (pintype "passive"))
      (node (ref "MC9") (pin "2") (pinfunction "2_2") (pintype "passive"))
      (node (ref "MR8") (pin "1") (pinfunction "1_1") (pintype "passive"))
    )
    (net (code "18") (name "C9") (class "Default")
      (node (ref "LED10") (pin "C") (pinfunction "C_C") (pintype "passive"))
      (node (ref "MR9") (pin "2") (pinfunction "2_2") (pintype "passive"))
      (node (ref "QB9") (pin "2") (pinfunction "S_2") (pintype "passive"))
      (node (ref "RP10") (pin "P$1") (pinfunction "1_P$1") (pintype "passive"))
      (node (ref "X5") (pin "P$2") (pinfunction "2_P$2") (pintype "passive"))
    )
    (net (code "19") (name "C9M") (class "Default")
      (node (ref "CD10") (pin "A") (pinfunction "A_A") (pintype "passive"))
      (node (ref "CD9") (pin "C") (pinfunction "C_C") (pintype "passive"))
      (node (ref "IC1") (pin "11") (pinfunction "C9_11") (pintype "bidirectional"))
      (node (ref "MC10") (pin "2") (pinfunction "2_2") (pintype "passive"))
      (node (ref "MC9") (pin "1") (pinfunction "1_1") (pintype "passive"))
      (node (ref "MR9") (pin "1") (pinfunction "1_1") (pintype "passive"))
    )
    (net (code "20") (name "C10") (class "Default")
      (node (ref "LED11") (pin "C") (pinfunction "C_C") (pintype "passive"))
      (node (ref "MR10") (pin "2") (pinfunction "2_2") (pintype "passive"))
      (node (ref "QB10") (pin "2") (pinfunction "S_2") (pintype "passive"))
      (node (ref "RP11") (pin "P$1") (pinfunction "1_P$1") (pintype "passive"))
      (node (ref "X5") (pin "P$9") (pinfunction "9_P$9") (pintype "passive"))
    )
    (net (code "21") (name "C10M") (class "Default")
      (node (ref "CD10") (pin "C") (pinfunction "C_C") (pintype "passive"))
      (node (ref "CD11") (pin "A") (pinfunction "A_A") (pintype "passive"))
      (node (ref "IC1") (pin "9") (pinfunction "C10_9") (pintype "bidirectional"))
      (node (ref "MC10") (pin "1") (pinfunction "1_1") (pintype "passive"))
      (node (ref "MC11") (pin "2") (pinfunction "2_2") (pintype "passive"))
      (node (ref "MR10") (pin "1") (pinfunction "1_1") (pintype "passive"))
    )
    (net (code "22") (name "C11") (class "Default")
      (node (ref "LED12") (pin "C") (pinfunction "C_C") (pintype "passive"))
      (node (ref "MR11") (pin "2") (pinfunction "2_2") (pintype "passive"))
      (node (ref "QB11") (pin "2") (pinfunction "S_2") (pintype "passive"))
      (node (ref "RP12") (pin "P$1") (pinfunction "1_P$1") (pintype "passive"))
      (node (ref "X5") (pin "P$1") (pinfunction "1_P$1") (pintype "passive"))
    )
    (net (code "23") (name "C11M") (class "Default")
      (node (ref "CD11") (pin "C") (pinfunction "C_C") (pintype "passive"))
      (node (ref "CD12") (pin "A") (pinfunction "A_A") (pintype "passive"))
      (node (ref "IC1") (pin "7") (pinfunction "C11_7") (pintype "bidirectional"))
      (node (ref "MC11") (pin "1") (pinfunction "1_1") (pintype "passive"))
      (node (ref "MC12") (pin "2") (pinfunction "2_2") (pintype "passive"))
      (node (ref "MR11") (pin "1") (pinfunction "1_1") (pintype "passive"))
    )
    (net (code "24") (name "C12") (class "Default")
      (node (ref "CS1") (pin "1") (pinfunction "1_1") (pintype "passive"))
      (node (ref "D4") (pin "C") (pinfunction "C_C") (pintype "passive"))
      (node (ref "IC1") (pin "4") (pinfunction "V+_4") (pintype "bidirectional"))
      (node (ref "MR12") (pin "2") (pinfunction "2_2") (pintype "passive"))
      (node (ref "QB12") (pin "2") (pinfunction "S_2") (pintype "passive"))
      (node (ref "RF1") (pin "2") (pinfunction "2_2") (pintype "passive"))
      (node (ref "X5") (pin "P$8") (pinfunction "8_P$8") (pintype "passive"))
    )
    (net (code "25") (name "C12M") (class "Default")
      (node (ref "CD12") (pin "C") (pinfunction "C_C") (pintype "passive"))
      (node (ref "IC1") (pin "5") (pinfunction "C12_5") (pintype "bidirectional"))
      (node (ref "MC12") (pin "1") (pinfunction "1_1") (pintype "passive"))
      (node (ref "MR12") (pin "1") (pinfunction "1_1") (pintype "passive"))
    )
    (net (code "26") (name "CSBB") (class "Default")
      (node (ref "IC1") (pin "44") (pinfunction "CSBI_44") (pintype "bidirectional"))
      (node (ref "R6") (pin "1") (pinfunction "1_1") (pintype "passive"))
    )
    (net (code "27") (name "CSBT") (class "Default")
      (node (ref "D1") (pin "C") (pinfunction "C_C") (pintype "passive"))
      (node (ref "IC1") (pin "1") (pinfunction "CSBO_1") (pintype "bidirectional"))
    )
    (net (code "28") (name "FSM") (class "Default")
      (node (ref "CF1") (pin "1") (pinfunction "1_1") (pintype "passive"))
      (node (ref "IC4") (pin "11") (pinfunction "X3_11") (pintype "bidirectional"))
      (node (ref "RF1") (pin "1") (pinfunction "1_1") (pintype "passive"))
      (node (ref "RF2") (pin "2") (pinfunction "2_2") (pintype "passive"))
    )
    (net (code "29") (name "GND") (class "Default")
      (node (ref "C1") (pin "2") (pinfunction "2_2") (pintype "passive"))
      (node (ref "C12") (pin "2") (pinfunction "2_2") (pintype "passive"))
      (node (ref "C2") (pin "2") (pinfunction "2_2") (pintype "passive"))
      (node (ref "C25") (pin "2") (pinfunction "2_2") (pintype "passive"))
      (node (ref "C3") (pin "2") (pinfunction "2_2") (pintype "passive"))
      (node (ref "C4") (pin "2") (pinfunction "2_2") (pintype "passive"))
      (node (ref "C5") (pin "2") (pinfunction "2_2") (pintype "passive"))
      (node (ref "C6") (pin "2") (pinfunction "2_2") (pintype "passive"))
      (node (ref "C7") (pin "2") (pinfunction "2_2") (pintype "passive"))
      (node (ref "C9") (pin "2") (pinfunction "2_2") (pintype "passive"))
      (node (ref "CD1") (pin "A") (pinfunction "A_A") (pintype "passive"))
      (node (ref "CF1") (pin "2") (pinfunction "2_2") (pintype "passive"))
      (node (ref "CS1") (pin "2") (pinfunction "2_2") (pintype "passive"))
      (node (ref "D4") (pin "A") (pinfunction "A_A") (pintype "passive"))
      (node (ref "IC1") (pin "29") (pinfunction "C0_29") (pintype "bidirectional"))
      (node (ref "IC1") (pin "30") (pinfunction "V-_30") (pintype "bidirectional"))
      (node (ref "IC2") (pin "2") (pinfunction "V-_2") (pintype "power_in"))
      (node (ref "IC3") (pin "4") (pinfunction "V-_4") (pintype "power_in"))
      (node (ref "IC4") (pin "6") (pinfunction "INH_6") (pintype "input"))
      (node (ref "IC4") (pin "7") (pinfunction "VEE_7") (pintype "power_in"))
      (node (ref "IC4") (pin "8") (pinfunction "GND_8") (pintype "power_in"))
      (node (ref "LED1") (pin "C") (pinfunction "C_C") (pintype "passive"))
      (node (ref "MC1") (pin "2") (pinfunction "2_2") (pintype "passive"))
      (node (ref "RF2") (pin "1") (pinfunction "1_1") (pintype "passive"))
      (node (ref "RP1") (pin "P$1") (pinfunction "1_P$1") (pintype "passive"))
      (node (ref "SJ1") (pin "3") (pinfunction "3_3") (pintype "passive"))
      (node (ref "SJ2") (pin "1") (pinfunction "1_1") (pintype "passive"))
      (node (ref "X3") (pin "2") (pinfunction "2_2") (pintype "passive"))
      (node (ref "X4") (pin "P$10") (pinfunction "10_P$10") (pintype "passive"))
      (node (ref "X4") (pin "P$11") (pinfunction "11_P$11") (pintype "passive"))
      (node (ref "X4") (pin "P$12") (pinfunction "12_P$12") (pintype "passive"))
      (node (ref "X4") (pin "P$7") (pinfunction "7_P$7") (pintype "passive"))
      (node (ref "X4") (pin "P$8") (pinfunction "8_P$8") (pintype "passive"))
      (node (ref "X4") (pin "P$9") (pinfunction "9_P$9") (pintype "passive"))
      (node (ref "X5") (pin "P$14") (pinfunction "14_P$14") (pintype "passive"))
      (node (ref "X5") (pin "P$7") (pinfunction "7_P$7") (pintype "passive"))
    )
    (net (code "30") (name "GPIO1") (class "Default")
      (node (ref "IC1") (pin "38") (pinfunction "GPIO1_38") (pintype "bidirectional"))
      (node (ref "IC4") (pin "10") (pinfunction "A_10") (pintype "input"))
      (node (ref "R22") (pin "1") (pinfunction "1_1") (pintype "passive"))
    )
    (net (code "31") (name "GPIO2") (class "Default")
      (node (ref "IC1") (pin "39") (pinfunction "GPIO2_39") (pintype "bidirectional"))
      (node (ref "IC4") (pin "9") (pinfunction "B_9") (pintype "input"))
      (node (ref "R21") (pin "1") (pinfunction "1_1") (pintype "passive"))
    )
    (net (code "32") (name "MUX1") (class "Default")
      (node (ref "IC3") (pin "3") (pinfunction "+IN_3") (pintype "input"))
      (node (ref "IC4") (pin "13") (pinfunction "X_13") (pintype "bidirectional"))
    )
    (net (code "33") (name "MUX2") (class "Default")
      (node (ref "IC3") (pin "5") (pinfunction "+IN_5") (pintype "input"))
      (node (ref "IC4") (pin "3") (pinfunction "Y_3") (pintype "bidirectional"))
    )
    (net (code "34") (name "Net-(D1-PadA)") (class "Default")
      (node (ref "D1") (pin "A") (pinfunction "A_A") (pintype "passive"))
      (node (ref "R3") (pin "1") (pinfunction "1_1") (pintype "passive"))
    )
    (net (code "35") (name "Net-(D2-PadA)") (class "Default")
      (node (ref "D2") (pin "A") (pinfunction "A_A") (pintype "passive"))
      (node (ref "R4") (pin "1") (pinfunction "1_1") (pintype "passive"))
    )
    (net (code "36") (name "Net-(D3-PadA)") (class "Default")
      (node (ref "D3") (pin "A") (pinfunction "A_A") (pintype "passive"))
      (node (ref "R5") (pin "1") (pinfunction "1_1") (pintype "passive"))
    )
    (net (code "37") (name "Net-(IC1-WDTB)") (class "Default")
      (node (ref "IC1") (pin "37") (pinfunction "WDTB_37") (pintype "bidirectional"))
      (node (ref "R9") (pin "2") (pinfunction "2_2") (pintype "passive"))
    )
    (net (code "38") (name "Net-(LED1-PadA)") (class "Default")
      (node (ref "LED1") (pin "A") (pinfunction "A_A") (pintype "passive"))
      (node (ref "R10") (pin "1") (pinfunction "1_1") (pintype "passive"))
    )
    (net (code "39") (name "Net-(LED2-PadA)") (class "Default")
      (node (ref "LED2") (pin "A") (pinfunction "A_A") (pintype "passive"))
      (node (ref "R11") (pin "1") (pinfunction "1_1") (pintype "passive"))
    )
    (net (code "40") (name "Net-(LED3-PadA)") (class "Default")
      (node (ref "LED3") (pin "A") (pinfunction "A_A") (pintype "passive"))
      (node (ref "R12") (pin "1") (pinfunction "1_1") (pintype "passive"))
    )
    (net (code "41") (name "Net-(LED4-PadA)") (class "Default")
      (node (ref "LED4") (pin "A") (pinfunction "A_A") (pintype "passive"))
      (node (ref "R13") (pin "1") (pinfunction "1_1") (pintype "passive"))
    )
    (net (code "42") (name "Net-(LED5-PadA)") (class "Default")
      (node (ref "LED5") (pin "A") (pinfunction "A_A") (pintype "passive"))
      (node (ref "R14") (pin "1") (pinfunction "1_1") (pintype "passive"))
    )
    (net (code "43") (name "Net-(LED6-PadA)") (class "Default")
      (node (ref "LED6") (pin "A") (pinfunction "A_A") (pintype "passive"))
      (node (ref "R19") (pin "1") (pinfunction "1_1") (pintype "passive"))
    )
    (net (code "44") (name "Net-(LED7-PadA)") (class "Default")
      (node (ref "LED7") (pin "A") (pinfunction "A_A") (pintype "passive"))
      (node (ref "R20") (pin "1") (pinfunction "1_1") (pintype "passive"))
    )
    (net (code "45") (name "Net-(LED8-PadA)") (class "Default")
      (node (ref "LED8") (pin "A") (pinfunction "A_A") (pintype "passive"))
      (node (ref "R23") (pin "1") (pinfunction "1_1") (pintype "passive"))
    )
    (net (code "46") (name "Net-(LED9-PadA)") (class "Default")
      (node (ref "LED9") (pin "A") (pinfunction "A_A") (pintype "passive"))
      (node (ref "R24") (pin "1") (pinfunction "1_1") (pintype "passive"))
    )
    (net (code "47") (name "Net-(LED10-PadA)") (class "Default")
      (node (ref "LED10") (pin "A") (pinfunction "A_A") (pintype "passive"))
      (node (ref "R25") (pin "1") (pinfunction "1_1") (pintype "passive"))
    )
    (net (code "48") (name "Net-(LED11-PadA)") (class "Default")
      (node (ref "LED11") (pin "A") (pinfunction "A_A") (pintype "passive"))
      (node (ref "R26") (pin "1") (pinfunction "1_1") (pintype "passive"))
    )
    (net (code "49") (name "Net-(LED12-PadA)") (class "Default")
      (node (ref "LED12") (pin "A") (pinfunction "A_A") (pintype "passive"))
      (node (ref "R27") (pin "1") (pinfunction "1_1") (pintype "passive"))
    )
    (net (code "50") (name "Net-(QB1-D)") (class "Default")
      (node (ref "QB1") (pin "3") (pinfunction "D_3") (pintype "passive"))
      (node (ref "R10") (pin "2") (pinfunction "2_2") (pintype "passive"))
      (node (ref "RP1") (pin "P$2") (pinfunction "2_P$2") (pintype "passive"))
    )
    (net (code "51") (name "Net-(QB1-G)") (class "Default")
      (node (ref "GR1") (pin "2") (pinfunction "2_2") (pintype "passive"))
      (node (ref "QB1") (pin "1") (pinfunction "G_1") (pintype "passive"))
    )
    (net (code "52") (name "Net-(QB2-D)") (class "Default")
      (node (ref "QB2") (pin "3") (pinfunction "D_3") (pintype "passive"))
      (node (ref "R11") (pin "2") (pinfunction "2_2") (pintype "passive"))
      (node (ref "RP2") (pin "P$2") (pinfunction "2_P$2") (pintype "passive"))
    )
    (net (code "53") (name "Net-(QB2-G)") (class "Default")
      (node (ref "GR2") (pin "2") (pinfunction "2_2") (pintype "passive"))
      (node (ref "QB2") (pin "1") (pinfunction "G_1") (pintype "passive"))
    )
    (net (code "54") (name "Net-(QB3-D)") (class "Default")
      (node (ref "QB3") (pin "3") (pinfunction "D_3") (pintype "passive"))
      (node (ref "R12") (pin "2") (pinfunction "2_2") (pintype "passive"))
      (node (ref "RP3") (pin "P$2") (pinfunction "2_P$2") (pintype "passive"))
    )
    (net (code "55") (name "Net-(QB3-G)") (class "Default")
      (node (ref "GR3") (pin "2") (pinfunction "2_2") (pintype "passive"))
      (node (ref "QB3") (pin "1") (pinfunction "G_1") (pintype "passive"))
    )
    (net (code "56") (name "Net-(QB4-D)") (class "Default")
      (node (ref "QB4") (pin "3") (pinfunction "D_3") (pintype "passive"))
      (node (ref "R13") (pin "2") (pinfunction "2_2") (pintype "passive"))
      (node (ref "RP4") (pin "P$2") (pinfunction "2_P$2") (pintype "passive"))
    )
    (net (code "57") (name "Net-(QB4-G)") (class "Default")
      (node (ref "GR4") (pin "2") (pinfunction "2_2") (pintype "passive"))
      (node (ref "QB4") (pin "1") (pinfunction "G_1") (pintype "passive"))
    )
    (net (code "58") (name "Net-(QB5-D)") (class "Default")
      (node (ref "QB5") (pin "3") (pinfunction "D_3") (pintype "passive"))
      (node (ref "R14") (pin "2") (pinfunction "2_2") (pintype "passive"))
      (node (ref "RP5") (pin "P$2") (pinfunction "2_P$2") (pintype "passive"))
    )
    (net (code "59") (name "Net-(QB5-G)") (class "Default")
      (node (ref "GR5") (pin "2") (pinfunction "2_2") (pintype "passive"))
      (node (ref "QB5") (pin "1") (pinfunction "G_1") (pintype "passive"))
    )
    (net (code "60") (name "Net-(QB6-D)") (class "Default")
      (node (ref "QB6") (pin "3") (pinfunction "D_3") (pintype "passive"))
      (node (ref "R19") (pin "2") (pinfunction "2_2") (pintype "passive"))
      (node (ref "RP6") (pin "P$2") (pinfunction "2_P$2") (pintype "passive"))
    )
    (net (code "61") (name "Net-(QB6-G)") (class "Default")
      (node (ref "GR6") (pin "2") (pinfunction "2_2") (pintype "passive"))
      (node (ref "QB6") (pin "1") (pinfunction "G_1") (pintype "passive"))
    )
    (net (code "62") (name "Net-(QB7-D)") (class "Default")
      (node (ref "QB7") (pin "3") (pinfunction "D_3") (pintype "passive"))
      (node (ref "R20") (pin "2") (pinfunction "2_2") (pintype "passive"))
      (node (ref "RP7") (pin "P$2") (pinfunction "2_P$2") (pintype "passive"))
    )
    (net (code "63") (name "Net-(QB7-G)") (class "Default")
      (node (ref "GR7") (pin "2") (pinfunction "2_2") (pintype "passive"))
      (node (ref "QB7") (pin "1") (pinfunction "G_1") (pintype "passive"))
    )
    (net (code "64") (name "Net-(QB8-D)") (class "Default")
      (node (ref "QB8") (pin "3") (pinfunction "D_3") (pintype "passive"))
      (node (ref "R23") (pin "2") (pinfunction "2_2") (pintype "passive"))
      (node (ref "RP8") (pin "P$2") (pinfunction "2_P$2") (pintype "passive"))
    )
    (net (code "65") (name "Net-(QB8-G)") (class "Default")
      (node (ref "GR8") (pin "2") (pinfunction "2_2") (pintype "passive"))
      (node (ref "QB8") (pin "1") (pinfunction "G_1") (pintype "passive"))
    )
    (net (code "66") (name "Net-(QB9-D)") (class "Default")
      (node (ref "QB9") (pin "3") (pinfunction "D_3") (pintype "passive"))
      (node (ref "R24") (pin "2") (pinfunction "2_2") (pintype "passive"))
      (node (ref "RP9") (pin "P$2") (pinfunction "2_P$2") (pintype "passive"))
    )
    (net (code "67") (name "Net-(QB9-G)") (class "Default")
      (node (ref "GR9") (pin "2") (pinfunction "2_2") (pintype "passive"))
      (node (ref "QB9") (pin "1") (pinfunction "G_1") (pintype "passive"))
    )
    (net (code "68") (name "Net-(QB10-D)") (class "Default")
      (node (ref "QB10") (pin "3") (pinfunction "D_3") (pintype "passive"))
      (node (ref "R25") (pin "2") (pinfunction "2_2") (pintype "passive"))
      (node (ref "RP10") (pin "P$2") (pinfunction "2_P$2") (pintype "passive"))
    )
    (net (code "69") (name "Net-(QB10-G)") (class "Default")
      (node (ref "GR10") (pin "2") (pinfunction "2_2") (pintype "passive"))
      (node (ref "QB10") (pin "1") (pinfunction "G_1") (pintype "passive"))
    )
    (net (code "70") (name "Net-(QB11-D)") (class "Default")
      (node (ref "QB11") (pin "3") (pinfunction "D_3") (pintype "passive"))
      (node (ref "R26") (pin "2") (pinfunction "2_2") (pintype "passive"))
      (node (ref "RP11") (pin "P$2") (pinfunction "2_P$2") (pintype "passive"))
    )
    (net (code "71") (name "Net-(QB11-G)") (class "Default")
      (node (ref "GR11") (pin "2") (pinfunction "2_2") (pintype "passive"))
      (node (ref "QB11") (pin "1") (pinfunction "G_1") (pintype "passive"))
    )
    (net (code "72") (name "Net-(QB12-D)") (class "Default")
      (node (ref "QB12") (pin "3") (pinfunction "D_3") (pintype "passive"))
      (node (ref "R27") (pin "2") (pinfunction "2_2") (pintype "passive"))
      (node (ref "RP12") (pin "P$2") (pinfunction "2_P$2") (pintype "passive"))
    )
    (net (code "73") (name "Net-(QB12-G)") (class "Default")
      (node (ref "GR12") (pin "2") (pinfunction "2_2") (pintype "passive"))
      (node (ref "QB12") (pin "1") (pinfunction "G_1") (pintype "passive"))
    )
    (net (code "74") (name "Net-(R3-Pad2)") (class "Default")
      (node (ref "R3") (pin "2") (pinfunction "2_2") (pintype "passive"))
      (node (ref "X1") (pin "1") (pinfunction "1_1") (pintype "passive"))
    )
    (net (code "75") (name "Net-(R4-Pad2)") (class "Default")
      (node (ref "R4") (pin "2") (pinfunction "2_2") (pintype "passive"))
      (node (ref "X1") (pin "2") (pinfunction "2_2") (pintype "passive"))
    )
    (net (code "76") (name "Net-(R5-Pad2)") (class "Default")
      (node (ref "R5") (pin "2") (pinfunction "2_2") (pintype "passive"))
      (node (ref "X1") (pin "3") (pinfunction "3_3") (pintype "passive"))
    )
    (net (code "77") (name "Net-(R6-Pad2)") (class "Default")
      (node (ref "R6") (pin "2") (pinfunction "2_2") (pintype "passive"))
      (node (ref "X2") (pin "1") (pinfunction "1_1") (pintype "passive"))
    )
    (net (code "78") (name "Net-(R7-Pad2)") (class "Default")
      (node (ref "R7") (pin "2") (pinfunction "2_2") (pintype "passive"))
      (node (ref "X2") (pin "2") (pinfunction "2_2") (pintype "passive"))
    )
    (net (code "79") (name "Net-(R8-Pad2)") (class "Default")
      (node (ref "R8") (pin "2") (pinfunction "2_2") (pintype "passive"))
      (node (ref "X2") (pin "3") (pinfunction "3_3") (pintype "passive"))
    )
    (net (code "80") (name "S1") (class "Default")
      (node (ref "GR1") (pin "1") (pinfunction "1_1") (pintype "passive"))
      (node (ref "IC1") (pin "28") (pinfunction "S1_28") (pintype "bidirectional"))
    )
    (net (code "81") (name "S2") (class "Default")
      (node (ref "GR2") (pin "1") (pinfunction "1_1") (pintype "passive"))
      (node (ref "IC1") (pin "26") (pinfunction "S2_26") (pintype "bidirectional"))
    )
    (net (code "82") (name "S3") (class "Default")
      (node (ref "GR3") (pin "1") (pinfunction "1_1") (pintype "passive"))
      (node (ref "IC1") (pin "24") (pinfunction "S3_24") (pintype "bidirectional"))
    )
    (net (code "83") (name "S4") (class "Default")
      (node (ref "GR4") (pin "1") (pinfunction "1_1") (pintype "passive"))
      (node (ref "IC1") (pin "22") (pinfunction "S4_22") (pintype "bidirectional"))
    )
    (net (code "84") (name "S5") (class "Default")
      (node (ref "GR5") (pin "1") (pinfunction "1_1") (pintype "passive"))
      (node (ref "IC1") (pin "20") (pinfunction "S5_20") (pintype "bidirectional"))
    )
    (net (code "85") (name "S6") (class "Default")
      (node (ref "GR6") (pin "1") (pinfunction "1_1") (pintype "passive"))
      (node (ref "IC1") (pin "18") (pinfunction "S6_18") (pintype "bidirectional"))
    )
    (net (code "86") (name "S7") (class "Default")
      (node (ref "GR7") (pin "1") (pinfunction "1_1") (pintype "passive"))
      (node (ref "IC1") (pin "16") (pinfunction "S7_16") (pintype "bidirectional"))
    )
    (net (code "87") (name "S8") (class "Default")
      (node (ref "GR8") (pin "1") (pinfunction "1_1") (pintype "passive"))
      (node (ref "IC1") (pin "14") (pinfunction "S8_14") (pintype "bidirectional"))
    )
    (net (code "88") (name "S9") (class "Default")
      (node (ref "GR9") (pin "1") (pinfunction "1_1") (pintype "passive"))
      (node (ref "IC1") (pin "12") (pinfunction "S9_12") (pintype "bidirectional"))
    )
    (net (code "89") (name "S10") (class "Default")
      (node (ref "GR10") (pin "1") (pinfunction "1_1") (pintype "passive"))
      (node (ref "IC1") (pin "10") (pinfunction "S10_10") (pintype "bidirectional"))
    )
    (net (code "90") (name "S11") (class "Default")
      (node (ref "GR11") (pin "1") (pinfunction "1_1") (pintype "passive"))
      (node (ref "IC1") (pin "8") (pinfunction "S11_8") (pintype "bidirectional"))
    )
    (net (code "91") (name "S12") (class "Default")
      (node (ref "GR12") (pin "1") (pinfunction "1_1") (pintype "passive"))
      (node (ref "IC1") (pin "6") (pinfunction "S12_6") (pintype "bidirectional"))
    )
    (net (code "92") (name "SCKB") (class "Default")
      (node (ref "IC1") (pin "41") (pinfunction "SCKI_41") (pintype "bidirectional"))
      (node (ref "R8") (pin "1") (pinfunction "1_1") (pintype "passive"))
    )
    (net (code "93") (name "SCKT") (class "Default")
      (node (ref "D3") (pin "C") (pinfunction "C_C") (pintype "passive"))
      (node (ref "IC1") (pin "3") (pinfunction "SCKO_3") (pintype "bidirectional"))
    )
    (net (code "94") (name "SDIB") (class "Default")
      (node (ref "IC1") (pin "42") (pinfunction "SDI_42") (pintype "bidirectional"))
      (node (ref "R7") (pin "1") (pinfunction "1_1") (pintype "passive"))
    )
    (net (code "95") (name "SDOB") (class "Default")
      (node (ref "IC1") (pin "43") (pinfunction "SDO_43") (pintype "bidirectional"))
      (node (ref "X3") (pin "1") (pinfunction "1_1") (pintype "passive"))
    )
    (net (code "96") (name "SDOT") (class "Default")
      (node (ref "D2") (pin "C") (pinfunction "C_C") (pintype "passive"))
      (node (ref "IC1") (pin "2") (pinfunction "SDOI_2") (pintype "bidirectional"))
    )
    (net (code "97") (name "TOS") (class "Default")
      (node (ref "IC1") (pin "36") (pinfunction "TOS_36") (pintype "bidirectional"))
      (node (ref "SJ2") (pin "2") (pinfunction "2_2") (pintype "passive"))
    )
    (net (code "98") (name "TSM1") (class "Default")
      (node (ref "C25") (pin "1") (pinfunction "1_1") (pintype "passive"))
      (node (ref "IC4") (pin "5") (pinfunction "Y1_5") (pintype "bidirectional"))
      (node (ref "R15") (pin "2") (pinfunction "2_2") (pintype "passive"))
      (node (ref "X4") (pin "P$1") (pinfunction "1_P$1") (pintype "passive"))
    )
    (net (code "99") (name "TSM2") (class "Default")
      (node (ref "C1") (pin "1") (pinfunction "1_1") (pintype "passive"))
      (node (ref "IC4") (pin "2") (pinfunction "Y2_2") (pintype "bidirectional"))
      (node (ref "R16") (pin "2") (pinfunction "2_2") (pintype "passive"))
      (node (ref "X4") (pin "P$2") (pinfunction "2_P$2") (pintype "passive"))
    )
    (net (code "100") (name "TSM3") (class "Default")
      (node (ref "C2") (pin "1") (pinfunction "1_1") (pintype "passive"))
      (node (ref "IC4") (pin "1") (pinfunction "Y0_1") (pintype "bidirectional"))
      (node (ref "R17") (pin "2") (pinfunction "2_2") (pintype "passive"))
      (node (ref "X4") (pin "P$3") (pinfunction "3_P$3") (pintype "passive"))
    )
    (net (code "101") (name "TSM4") (class "Default")
      (node (ref "C3") (pin "1") (pinfunction "1_1") (pintype "passive"))
      (node (ref "IC4") (pin "15") (pinfunction "X2_15") (pintype "bidirectional"))
      (node (ref "R18") (pin "2") (pinfunction "2_2") (pintype "passive"))
      (node (ref "X4") (pin "P$4") (pinfunction "4_P$4") (pintype "passive"))
    )
    (net (code "102") (name "TSM5") (class "Default")
      (node (ref "C6") (pin "1") (pinfunction "1_1") (pintype "passive"))
      (node (ref "IC4") (pin "12") (pinfunction "X0_12") (pintype "bidirectional"))
      (node (ref "R1") (pin "2") (pinfunction "2_2") (pintype "passive"))
      (node (ref "X4") (pin "P$6") (pinfunction "6_P$6") (pintype "passive"))
    )
    (net (code "103") (name "TSM6") (class "Default")
      (node (ref "C5") (pin "1") (pinfunction "1_1") (pintype "passive"))
      (node (ref "IC4") (pin "14") (pinfunction "X1_14") (pintype "bidirectional"))
      (node (ref "R2") (pin "2") (pinfunction "2_2") (pintype "passive"))
      (node (ref "X4") (pin "P$5") (pinfunction "5_P$5") (pintype "passive"))
    )
    (net (code "104") (name "VMODE") (class "Default")
      (node (ref "IC1") (pin "40") (pinfunction "VMODE_40") (pintype "bidirectional"))
      (node (ref "SJ1") (pin "2") (pinfunction "2_2") (pintype "passive"))
    )
    (net (code "105") (name "VREF") (class "Default")
      (node (ref "C7") (pin "1") (pinfunction "1_1") (pintype "passive"))
      (node (ref "IC1") (pin "34") (pinfunction "VREF_34") (pintype "bidirectional"))
      (node (ref "IC2") (pin "3") (pinfunction "+IN_3") (pintype "input"))
    )
    (net (code "106") (name "VREFP") (class "Default")
      (node (ref "IC2") (pin "1") (pinfunction "OUT_1") (pintype "output"))
      (node (ref "IC2") (pin "4") (pinfunction "-IN_4") (pintype "input"))
      (node (ref "R1") (pin "1") (pinfunction "1_1") (pintype "passive"))
      (node (ref "R15") (pin "1") (pinfunction "1_1") (pintype "passive"))
      (node (ref "R16") (pin "1") (pinfunction "1_1") (pintype "passive"))
      (node (ref "R17") (pin "1") (pinfunction "1_1") (pintype "passive"))
      (node (ref "R18") (pin "1") (pinfunction "1_1") (pintype "passive"))
      (node (ref "R2") (pin "1") (pinfunction "1_1") (pintype "passive"))
    )
    (net (code "107") (name "VTEMP1") (class "Default")
      (node (ref "IC1") (pin "32") (pinfunction "VTEMP1_32") (pintype "bidirectional"))
      (node (ref "IC3") (pin "1") (pinfunction "OUT_1") (pintype "output"))
      (node (ref "IC3") (pin "2") (pinfunction "-IN_2") (pintype "input"))
    )
    (net (code "108") (name "VTEMP2") (class "Default")
      (node (ref "IC1") (pin "33") (pinfunction "VTEMP2_33") (pintype "bidirectional"))
      (node (ref "IC3") (pin "6") (pinfunction "-IN_6") (pintype "input"))
      (node (ref "IC3") (pin "7") (pinfunction "OUT_7") (pintype "output"))
    )
    (net (code "109") (name "unconnected-(IC4A-Y3-Pad4)") (class "Default")
      (node (ref "IC4") (pin "4") (pinfunction "Y3_4") (pintype "bidirectional"))
    )
  )
)
